# HVchannel.net
KiCad netlist of a schematic drawn in Altium Designer
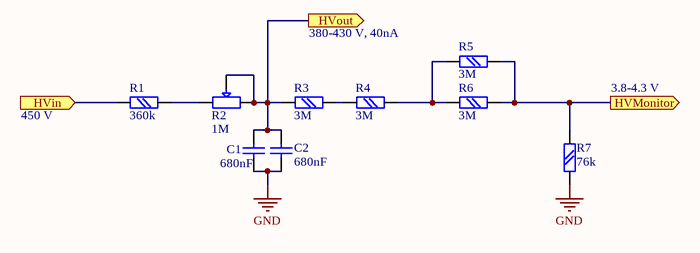
[diagram p0: HVchannel.SchDoc]

(export (version "E")
  (design (tool "Eeschema 10.0.6"))
  (components
    (comp (ref "C1")
      (value "680nF")
      (footprint "C20P0_4")
      (description "Capacitor")
      (fields (field (name "PUBLISHER") "Altium Limited"))
      (libsource (lib "Miscellaneous Devices") (part "Cap"))
    )
    (comp (ref "C2")
      (value "680nF")
      (footprint "C20P0_4")
      (description "Capacitor")
      (fields (field (name "PUBLISHER") "Altium Limited"))
      (libsource (lib "Miscellaneous Devices") (part "Cap"))
    )
    (comp (ref "R1") (value "360k") (footprint "chip0805") (libsource (lib "vDevice") (part "R")))
    (comp (ref "R2") (value "1M") (footprint "SH-R114S") (libsource (lib "vDevice") (part "R VAR")))
    (comp (ref "R3") (value "3M") (footprint "chip0805") (libsource (lib "vDevice") (part "R")))
    (comp (ref "R4") (value "3M") (footprint "chip0805") (libsource (lib "vDevice") (part "R")))
    (comp (ref "R5") (value "3M") (footprint "chip0805") (libsource (lib "vDevice") (part "R")))
    (comp (ref "R6") (value "3M") (footprint "chip0805") (libsource (lib "vDevice") (part "R")))
    (comp (ref "R7") (value "76k") (footprint "chip0805") (libsource (lib "vDevice") (part "R")))
  )
  (nets
    (net (code "1") (name "/HVMonitor") (class "Default")
      (node (ref "R5") (pin "2") (pinfunction "2_2") (pintype "passive"))
      (node (ref "R6") (pin "2") (pinfunction "2_2") (pintype "passive"))
      (node (ref "R7") (pin "1") (pinfunction "1_1") (pintype "passive"))
    )
    (net (code "2") (name "/HVin") (class "Default")
      (node (ref "R1") (pin "1") (pinfunction "1_1") (pintype "passive"))
    )
    (net (code "3") (name "/HVout") (class "Default")
      (node (ref "C1") (pin "2") (pinfunction "2_2") (pintype "passive"))
      (node (ref "C2") (pin "2") (pinfunction "2_2") (pintype "passive"))
      (node (ref "R2") (pin "2") (pinfunction "2_2") (pintype "passive"))
      (node (ref "R2") (pin "3") (pinfunction "3_3") (pintype "passive"))
      (node (ref "R3") (pin "1") (pinfunction "1_1") (pintype "passive"))
    )
    (net (code "4") (name "GND") (class "Default")
      (node (ref "C1") (pin "1") (pinfunction "1_1") (pintype "passive"))
      (node (ref "C2") (pin "1") (pinfunction "1_1") (pintype "passive"))
      (node (ref "R7") (pin "2") (pinfunction "2_2") (pintype "passive"))
    )
    (net (code "5") (name "Net-(R1-Pad2)") (class "Default")
      (node (ref "R1") (pin "2") (pinfunction "2_2") (pintype "passive"))
      (node (ref "R2") (pin "1") (pinfunction "1_1") (pintype "passive"))
    )
    (net (code "6") (name "Net-(R3-Pad2)") (class "Default")
      (node (ref "R3") (pin "2") (pinfunction "2_2") (pintype "passive"))
      (node (ref "R4") (pin "1") (pinfunction "1_1") (pintype "passive"))
    )
    (net (code "7") (name "Net-(R4-Pad2)") (class "Default")
      (node (ref "R4") (pin "2") (pinfunction "2_2") (pintype "passive"))
      (node (ref "R5") (pin "1") (pinfunction "1_1") (pintype "passive"))
      (node (ref "R6") (pin "1") (pinfunction "1_1") (pintype "passive"))
    )
  )
)
